# scHnRk_2.net
KiCad netlist of a schematic drawn in EAGLE
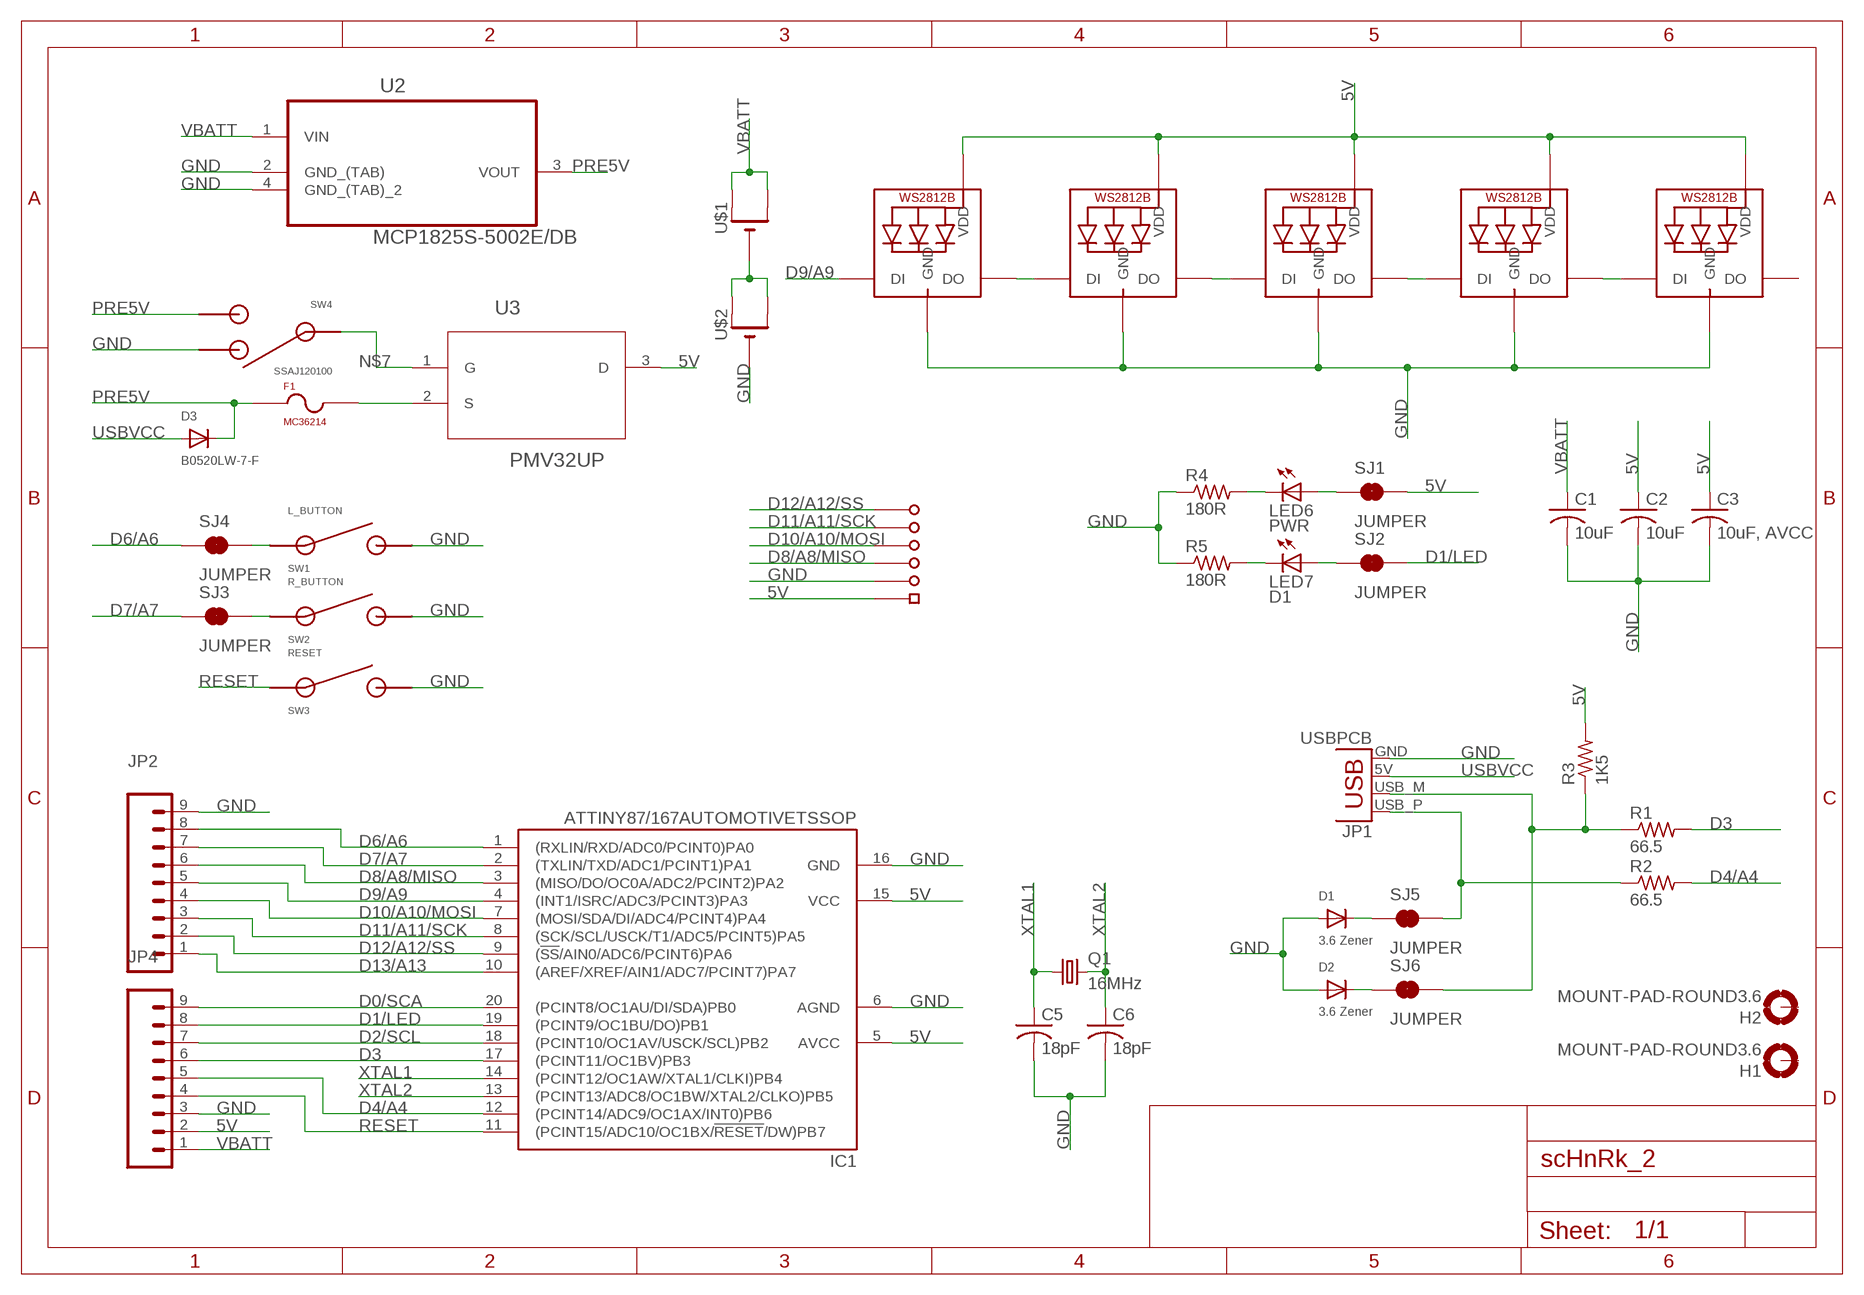
[diagram p0: schematic, sheet 1]

(export (version "E")
  (design (tool "Eeschema 10.0.6"))
  (components
    (comp (ref "C1")
      (value "10uF")
      (footprint "eagle-import:C1206K")
      (libsource (lib "eagle-import") (part "C-USC1206K"))
    )
    (comp (ref "C2")
      (value "10uF")
      (footprint "eagle-import:C1206K")
      (libsource (lib "eagle-import") (part "C-USC1206K"))
    )
    (comp (ref "C3")
      (value "10uF, AVCC")
      (footprint "eagle-import:C1206K")
      (libsource (lib "eagle-import") (part "C-USC1206K"))
    )
    (comp (ref "C5")
      (value "18pF")
      (footprint "eagle-import:C0603K")
      (libsource (lib "eagle-import") (part "C-USC0603K"))
    )
    (comp (ref "C6")
      (value "18pF")
      (footprint "eagle-import:C0603K")
      (libsource (lib "eagle-import") (part "C-USC0603K"))
    )
    (comp (ref "D1")
      (value "3.6 Zener")
      (footprint "eagle-import:SOD-523")
      (libsource (lib "eagle-import") (part "DIODESOD-523"))
    )
    (comp (ref "D2")
      (value "3.6 Zener")
      (footprint "eagle-import:SOD-523")
      (libsource (lib "eagle-import") (part "DIODESOD-523"))
    )
    (comp (ref "D3")
      (value "B0520LW-7-F")
      (footprint "eagle-import:SOD-123")
      (libsource (lib "eagle-import") (part "DIODESOD-123"))
    )
    (comp (ref "F1")
      (value "MC36214")
      (footprint "eagle-import:MC36214")
      (libsource (lib "eagle-import") (part "MC36214"))
    )
    (comp (ref "H1")
      (value "MOUNT-PAD-ROUND3.6")
      (footprint "eagle-import:3,6-PAD")
      (libsource (lib "eagle-import") (part "MOUNT-PAD-ROUND3.6"))
    )
    (comp (ref "H2")
      (value "MOUNT-PAD-ROUND3.6")
      (footprint "eagle-import:3,6-PAD")
      (libsource (lib "eagle-import") (part "MOUNT-PAD-ROUND3.6"))
    )
    (comp (ref "IC1")
      (value "ATTINY87/167AUTOMOTIVETSSOP")
      (footprint "eagle-import:TSSOP20")
      (libsource (lib "eagle-import") (part "ATTINY87/167AUTOMOTIVETSSOP"))
    )
    (comp (ref "JP1")
      (value "USBPCB")
      (footprint "eagle-import:USB-A-PCB")
      (libsource (lib "eagle-import") (part "USBPCB"))
    )
    (comp (ref "JP2")
      (value "M09")
      (footprint "eagle-import:1X09")
      (libsource (lib "eagle-import") (part "M09"))
    )
    (comp (ref "JP4")
      (value "M09")
      (footprint "eagle-import:1X09")
      (libsource (lib "eagle-import") (part "M09"))
    )
    (comp (ref "LED1")
      (value "WS2812B5050")
      (footprint "eagle-import:WS2812B")
      (libsource (lib "eagle-import") (part "WS2812B5050"))
    )
    (comp (ref "LED2")
      (value "WS2812B5050")
      (footprint "eagle-import:WS2812B")
      (libsource (lib "eagle-import") (part "WS2812B5050"))
    )
    (comp (ref "LED3")
      (value "WS2812B5050")
      (footprint "eagle-import:WS2812B")
      (libsource (lib "eagle-import") (part "WS2812B5050"))
    )
    (comp (ref "LED4")
      (value "WS2812B5050")
      (footprint "eagle-import:WS2812B")
      (libsource (lib "eagle-import") (part "WS2812B5050"))
    )
    (comp (ref "LED5")
      (value "WS2812B5050")
      (footprint "eagle-import:WS2812B")
      (libsource (lib "eagle-import") (part "WS2812B5050"))
    )
    (comp (ref "LED6")
      (value "PWR")
      (footprint "eagle-import:CHIPLED_0603")
      (libsource (lib "eagle-import") (part "LEDCHIPLED_0603"))
    )
    (comp (ref "LED7")
      (value "D1")
      (footprint "eagle-import:CHIPLED_0603")
      (libsource (lib "eagle-import") (part "LEDCHIPLED_0603"))
    )
    (comp (ref "Q1")
      (value "16MHz")
      (footprint "eagle-import:HC49UP")
      (libsource (lib "eagle-import") (part "CRYSTALHC49UP"))
    )
    (comp (ref "R1")
      (value "66.5")
      (footprint "eagle-import:R0603")
      (libsource (lib "eagle-import") (part "R-US_R0603"))
    )
    (comp (ref "R2")
      (value "66.5")
      (footprint "eagle-import:R0603")
      (libsource (lib "eagle-import") (part "R-US_R0603"))
    )
    (comp (ref "R3")
      (value "1K5")
      (footprint "eagle-import:R0603")
      (libsource (lib "eagle-import") (part "R-US_R0603"))
    )
    (comp (ref "R4")
      (value "180R")
      (footprint "eagle-import:R0603")
      (libsource (lib "eagle-import") (part "R-US_R0603"))
    )
    (comp (ref "R5")
      (value "180R")
      (footprint "eagle-import:R0603")
      (libsource (lib "eagle-import") (part "R-US_R0603"))
    )
    (comp (ref "SJ1")
      (value "JUMPER")
      (footprint "eagle-import:PAD-JUMPER-2-NC_BY_TRACE_YES_SILK")
      (libsource (lib "eagle-import") (part "JUMPER-PAD-2-NC_BY_TRACE"))
    )
    (comp (ref "SJ2")
      (value "JUMPER")
      (footprint "eagle-import:PAD-JUMPER-2-NC_BY_TRACE_YES_SILK")
      (libsource (lib "eagle-import") (part "JUMPER-PAD-2-NC_BY_TRACE"))
    )
    (comp (ref "SJ3")
      (value "JUMPER")
      (footprint "eagle-import:PAD-JUMPER-2-NC_BY_TRACE_YES_SILK")
      (libsource (lib "eagle-import") (part "JUMPER-PAD-2-NC_BY_TRACE"))
    )
    (comp (ref "SJ4")
      (value "JUMPER")
      (footprint "eagle-import:PAD-JUMPER-2-NC_BY_TRACE_YES_SILK")
      (libsource (lib "eagle-import") (part "JUMPER-PAD-2-NC_BY_TRACE"))
    )
    (comp (ref "SJ5")
      (value "JUMPER")
      (footprint "eagle-import:PAD-JUMPER-2-NC_BY_TRACE_YES_SILK")
      (libsource (lib "eagle-import") (part "JUMPER-PAD-2-NC_BY_TRACE"))
    )
    (comp (ref "SJ6")
      (value "JUMPER")
      (footprint "eagle-import:PAD-JUMPER-2-NC_BY_TRACE_YES_SILK")
      (libsource (lib "eagle-import") (part "JUMPER-PAD-2-NC_BY_TRACE"))
    )
    (comp (ref "SW1")
      (value "L_BUTTON")
      (footprint "eagle-import:SKRBAGE010")
      (libsource (lib "eagle-import") (part "SKRBAGE010"))
    )
    (comp (ref "SW2")
      (value "R_BUTTON")
      (footprint "eagle-import:SKRBAGE010")
      (libsource (lib "eagle-import") (part "SKRBAGE010"))
    )
    (comp (ref "SW3")
      (value "RESET")
      (footprint "eagle-import:SKRBAGE010")
      (libsource (lib "eagle-import") (part "SKRBAGE010"))
    )
    (comp (ref "SW4")
      (value "SSAJ120100")
      (footprint "eagle-import:SSAJ120100")
      (libsource (lib "eagle-import") (part "SSAJ120100"))
    )
    (comp (ref "TP1")
      (value "TP-R")
      (footprint "eagle-import:TP-R")
      (libsource (lib "eagle-import") (part "TP-R"))
    )
    (comp (ref "TP2")
      (value "TP-S")
      (footprint "eagle-import:TP_S")
      (libsource (lib "eagle-import") (part "TP-S"))
    )
    (comp (ref "TP3")
      (value "TP-R")
      (footprint "eagle-import:TP-R")
      (libsource (lib "eagle-import") (part "TP-R"))
    )
    (comp (ref "TP4")
      (value "TP-R")
      (footprint "eagle-import:TP-R")
      (libsource (lib "eagle-import") (part "TP-R"))
    )
    (comp (ref "TP5")
      (value "TP-R")
      (footprint "eagle-import:TP-R")
      (libsource (lib "eagle-import") (part "TP-R"))
    )
    (comp (ref "TP6")
      (value "TP-R")
      (footprint "eagle-import:TP-R")
      (libsource (lib "eagle-import") (part "TP-R"))
    )
    (comp (ref "U$1")
      (value "CR2032SMT")
      (footprint "eagle-import:CR2032-SMD")
      (libsource (lib "eagle-import") (part "CR2032SMT"))
    )
    (comp (ref "U$2")
      (value "CR2032SMT")
      (footprint "eagle-import:CR2032-SMD")
      (libsource (lib "eagle-import") (part "CR2032SMT"))
    )
    (comp (ref "U2")
      (value "MCP1825S-5002E/DB")
      (footprint "eagle-import:SOT230P700X180-4N")
      (libsource (lib "eagle-import") (part "MCP1825S-5002E/DB"))
    )
    (comp (ref "U3")
      (value "PMV32UP")
      (footprint "eagle-import:SOT95P230X110-3N")
      (libsource (lib "eagle-import") (part "PMV32UP"))
    )
  )
  (nets
    (net (code "1") (name "/5V") (class "Default")
      (node (ref "C2") (pin "1") (pinfunction "1_1") (pintype "passive"))
      (node (ref "C3") (pin "1") (pinfunction "1_1") (pintype "passive"))
      (node (ref "IC1") (pin "15") (pinfunction "VCC_15") (pintype "power_in"))
      (node (ref "IC1") (pin "5") (pinfunction "AVCC_5") (pintype "bidirectional"))
      (node (ref "JP4") (pin "2") (pinfunction "2_2") (pintype "passive"))
      (node (ref "LED1") (pin "1-VDD") (pinfunction "VDD_1-VDD") (pintype "power_in"))
      (node (ref "LED2") (pin "1-VDD") (pinfunction "VDD_1-VDD") (pintype "power_in"))
      (node (ref "LED3") (pin "1-VDD") (pinfunction "VDD_1-VDD") (pintype "power_in"))
      (node (ref "LED4") (pin "1-VDD") (pinfunction "VDD_1-VDD") (pintype "power_in"))
      (node (ref "LED5") (pin "1-VDD") (pinfunction "VDD_1-VDD") (pintype "power_in"))
      (node (ref "R3") (pin "2") (pinfunction "2_2") (pintype "passive"))
      (node (ref "SJ1") (pin "2") (pinfunction "2_2") (pintype "passive"))
      (node (ref "TP2") (pin "P$1") (pinfunction "P$1_P$1") (pintype "bidirectional"))
      (node (ref "U3") (pin "3") (pinfunction "D_3") (pintype "passive"))
    )
    (net (code "2") (name "/D0{slash}SCA") (class "Default")
      (node (ref "IC1") (pin "20") (pinfunction "(PCINT8/OC1AU/DI/SDA)PB0_20") (pintype "bidirectional"))
      (node (ref "JP4") (pin "9") (pinfunction "9_9") (pintype "passive"))
    )
    (net (code "3") (name "/D1{slash}LED") (class "Default")
      (node (ref "IC1") (pin "19") (pinfunction "(PCINT9/OC1BU/DO)PB1_19") (pintype "bidirectional"))
      (node (ref "JP4") (pin "8") (pinfunction "8_8") (pintype "passive"))
      (node (ref "SJ2") (pin "2") (pinfunction "2_2") (pintype "passive"))
    )
    (net (code "4") (name "/D2{slash}SCL") (class "Default")
      (node (ref "IC1") (pin "18") (pinfunction "(PCINT10/OC1AV/USCK/SCL)PB2_18") (pintype "bidirectional"))
      (node (ref "JP4") (pin "7") (pinfunction "7_7") (pintype "passive"))
    )
    (net (code "5") (name "/D3") (class "Default")
      (node (ref "IC1") (pin "17") (pinfunction "(PCINT11/OC1BV)PB3_17") (pintype "bidirectional"))
      (node (ref "JP4") (pin "6") (pinfunction "6_6") (pintype "passive"))
      (node (ref "R1") (pin "2") (pinfunction "2_2") (pintype "passive"))
    )
    (net (code "6") (name "/D4{slash}A4") (class "Default")
      (node (ref "IC1") (pin "12") (pinfunction "(PCINT14/ADC9/OC1AX/INT0)PB6_12") (pintype "bidirectional"))
      (node (ref "JP4") (pin "5") (pinfunction "5_5") (pintype "passive"))
      (node (ref "R2") (pin "2") (pinfunction "2_2") (pintype "passive"))
    )
    (net (code "7") (name "/D6{slash}A6") (class "Default")
      (node (ref "IC1") (pin "1") (pinfunction "(RXLIN/RXD/ADC0/PCINT0)PA0_1") (pintype "bidirectional"))
      (node (ref "JP2") (pin "8") (pinfunction "8_8") (pintype "passive"))
      (node (ref "SJ4") (pin "1") (pinfunction "1_1") (pintype "passive"))
    )
    (net (code "8") (name "/D7{slash}A7") (class "Default")
      (node (ref "IC1") (pin "2") (pinfunction "(TXLIN/TXD/ADC1/PCINT1)PA1_2") (pintype "bidirectional"))
      (node (ref "JP2") (pin "7") (pinfunction "7_7") (pintype "passive"))
      (node (ref "SJ3") (pin "1") (pinfunction "1_1") (pintype "passive"))
    )
    (net (code "9") (name "/D8{slash}A8{slash}MISO") (class "Default")
      (node (ref "IC1") (pin "3") (pinfunction "(MISO/DO/OC0A/ADC2/PCINT2)PA2_3") (pintype "bidirectional"))
      (node (ref "JP2") (pin "6") (pinfunction "6_6") (pintype "passive"))
      (node (ref "TP3") (pin "P$1") (pinfunction "P$1_P$1") (pintype "bidirectional"))
    )
    (net (code "10") (name "/D9{slash}A9") (class "Default")
      (node (ref "IC1") (pin "4") (pinfunction "(INT1/ISRC/ADC3/PCINT3)PA3_4") (pintype "bidirectional"))
      (node (ref "JP2") (pin "5") (pinfunction "5_5") (pintype "passive"))
      (node (ref "LED1") (pin "4-DIN") (pinfunction "DI_4-DIN") (pintype "input"))
    )
    (net (code "11") (name "/D10{slash}A10{slash}MOSI") (class "Default")
      (node (ref "IC1") (pin "7") (pinfunction "(MOSI/SDA/DI/ADC4/PCINT4)PA4_7") (pintype "bidirectional"))
      (node (ref "JP2") (pin "4") (pinfunction "4_4") (pintype "passive"))
      (node (ref "TP4") (pin "P$1") (pinfunction "P$1_P$1") (pintype "bidirectional"))
    )
    (net (code "12") (name "/D11{slash}A11{slash}SCK") (class "Default")
      (node (ref "IC1") (pin "8") (pinfunction "(SCK/SCL/USCK/T1/ADC5/PCINT5)PA5_8") (pintype "bidirectional"))
      (node (ref "JP2") (pin "3") (pinfunction "3_3") (pintype "passive"))
      (node (ref "TP5") (pin "P$1") (pinfunction "P$1_P$1") (pintype "bidirectional"))
    )
    (net (code "13") (name "/D12{slash}A12{slash}SS") (class "Default")
      (node (ref "IC1") (pin "9") (pinfunction "(~{SS}/AIN0/ADC6/PCINT6)PA6_9") (pintype "bidirectional"))
      (node (ref "JP2") (pin "2") (pinfunction "2_2") (pintype "passive"))
      (node (ref "TP6") (pin "P$1") (pinfunction "P$1_P$1") (pintype "bidirectional"))
    )
    (net (code "14") (name "/D13{slash}A13") (class "Default")
      (node (ref "IC1") (pin "10") (pinfunction "(AREF/XREF/AIN1/ADC7/PCINT7)PA7_10") (pintype "bidirectional"))
      (node (ref "JP2") (pin "1") (pinfunction "1_1") (pintype "passive"))
    )
    (net (code "15") (name "/GND") (class "Default")
      (node (ref "C1") (pin "2") (pinfunction "2_2") (pintype "passive"))
      (node (ref "C2") (pin "2") (pinfunction "2_2") (pintype "passive"))
      (node (ref "C3") (pin "2") (pinfunction "2_2") (pintype "passive"))
      (node (ref "C5") (pin "2") (pinfunction "2_2") (pintype "passive"))
      (node (ref "C6") (pin "2") (pinfunction "2_2") (pintype "passive"))
      (node (ref "D1") (pin "A") (pinfunction "A_A") (pintype "passive"))
      (node (ref "D2") (pin "A") (pinfunction "A_A") (pintype "passive"))
      (node (ref "IC1") (pin "16") (pinfunction "GND_16") (pintype "power_in"))
      (node (ref "IC1") (pin "6") (pinfunction "AGND_6") (pintype "bidirectional"))
      (node (ref "JP1") (pin "GND") (pinfunction "GND_GND") (pintype "bidirectional"))
      (node (ref "JP2") (pin "9") (pinfunction "9_9") (pintype "passive"))
      (node (ref "JP4") (pin "3") (pinfunction "3_3") (pintype "passive"))
      (node (ref "LED1") (pin "3-GND") (pinfunction "GND_3-GND") (pintype "power_in"))
      (node (ref "LED2") (pin "3-GND") (pinfunction "GND_3-GND") (pintype "power_in"))
      (node (ref "LED3") (pin "3-GND") (pinfunction "GND_3-GND") (pintype "power_in"))
      (node (ref "LED4") (pin "3-GND") (pinfunction "GND_3-GND") (pintype "power_in"))
      (node (ref "LED5") (pin "3-GND") (pinfunction "GND_3-GND") (pintype "power_in"))
      (node (ref "R4") (pin "1") (pinfunction "1_1") (pintype "passive"))
      (node (ref "R5") (pin "1") (pinfunction "1_1") (pintype "passive"))
      (node (ref "SW1") (pin "P$2") (pinfunction "P$2_P$2") (pintype "bidirectional"))
      (node (ref "SW1") (pin "P$4") (pinfunction "P$2_P$4") (pintype "bidirectional"))
      (node (ref "SW2") (pin "P$2") (pinfunction "P$2_P$2") (pintype "bidirectional"))
      (node (ref "SW2") (pin "P$4") (pinfunction "P$2_P$4") (pintype "bidirectional"))
      (node (ref "SW3") (pin "P$2") (pinfunction "P$2_P$2") (pintype "bidirectional"))
      (node (ref "SW3") (pin "P$4") (pinfunction "P$2_P$4") (pintype "bidirectional"))
      (node (ref "SW4") (pin "P$1") (pinfunction "P$1_P$1") (pintype "bidirectional"))
      (node (ref "TP1") (pin "P$1") (pinfunction "P$1_P$1") (pintype "bidirectional"))
      (node (ref "U$2") (pin "-") (pinfunction "-_-") (pintype "passive"))
      (node (ref "U2") (pin "2") (pinfunction "GND_(TAB)_2") (pintype "passive"))
      (node (ref "U2") (pin "4") (pinfunction "GND_(TAB)_2_4") (pintype "passive"))
    )
    (net (code "16") (name "/N$7") (class "Default")
      (node (ref "SW4") (pin "P$C") (pinfunction "P$C_P$C") (pintype "bidirectional"))
      (node (ref "U3") (pin "1") (pinfunction "G_1") (pintype "passive"))
    )
    (net (code "17") (name "/PRE5V") (class "Default")
      (node (ref "D3") (pin "C") (pinfunction "C_C") (pintype "passive"))
      (node (ref "F1") (pin "P$1") (pinfunction "P$1_P$1") (pintype "bidirectional"))
      (node (ref "SW4") (pin "P$2") (pinfunction "P$2_P$2") (pintype "bidirectional"))
      (node (ref "U2") (pin "3") (pinfunction "VOUT_3") (pintype "output"))
    )
    (net (code "18") (name "/RESET") (class "Default")
      (node (ref "IC1") (pin "11") (pinfunction "(PCINT15/ADC10/OC1BX/~{RESET}/DW)PB7_11") (pintype "bidirectional"))
      (node (ref "JP4") (pin "4") (pinfunction "4_4") (pintype "passive"))
      (node (ref "SW3") (pin "P$1") (pinfunction "P$1_P$1") (pintype "bidirectional"))
      (node (ref "SW3") (pin "P$3") (pinfunction "P$1_P$3") (pintype "bidirectional"))
    )
    (net (code "19") (name "/USBVCC") (class "Default")
      (node (ref "D3") (pin "A") (pinfunction "A_A") (pintype "passive"))
      (node (ref "JP1") (pin "5V") (pinfunction "VBUS_5V") (pintype "bidirectional"))
    )
    (net (code "20") (name "/VBATT") (class "Default")
      (node (ref "C1") (pin "1") (pinfunction "1_1") (pintype "passive"))
      (node (ref "JP4") (pin "1") (pinfunction "1_1") (pintype "passive"))
      (node (ref "U$1") (pin "+$1") (pinfunction "+_+$1") (pintype "passive"))
      (node (ref "U$1") (pin "+$2") (pinfunction "+1_+$2") (pintype "passive"))
      (node (ref "U2") (pin "1") (pinfunction "VIN_1") (pintype "input"))
    )
    (net (code "21") (name "/XTAL1") (class "Default")
      (node (ref "C5") (pin "1") (pinfunction "1_1") (pintype "passive"))
      (node (ref "IC1") (pin "14") (pinfunction "(PCINT12/OC1AW/XTAL1/CLKI)PB4_14") (pintype "bidirectional"))
      (node (ref "Q1") (pin "1") (pinfunction "1_1") (pintype "passive"))
    )
    (net (code "22") (name "/XTAL2") (class "Default")
      (node (ref "C6") (pin "1") (pinfunction "1_1") (pintype "passive"))
      (node (ref "IC1") (pin "13") (pinfunction "(PCINT13/ADC8/OC1BW/XTAL2/CLKO)PB5_13") (pintype "bidirectional"))
      (node (ref "Q1") (pin "2") (pinfunction "2_2") (pintype "passive"))
    )
    (net (code "23") (name "Net-(D1-C)") (class "Default")
      (node (ref "D1") (pin "K") (pinfunction "C_K") (pintype "passive"))
      (node (ref "SJ5") (pin "1") (pinfunction "1_1") (pintype "passive"))
    )
    (net (code "24") (name "Net-(D2-C)") (class "Default")
      (node (ref "D2") (pin "K") (pinfunction "C_K") (pintype "passive"))
      (node (ref "SJ6") (pin "1") (pinfunction "1_1") (pintype "passive"))
    )
    (net (code "25") (name "Net-(JP1-D+)") (class "Default")
      (node (ref "JP1") (pin "USB_P") (pinfunction "D+_USB_P") (pintype "bidirectional"))
      (node (ref "R2") (pin "1") (pinfunction "1_1") (pintype "passive"))
      (node (ref "SJ5") (pin "2") (pinfunction "2_2") (pintype "passive"))
    )
    (net (code "26") (name "Net-(JP1-D-)") (class "Default")
      (node (ref "JP1") (pin "USB_M") (pinfunction "D-_USB_M") (pintype "bidirectional"))
      (node (ref "R1") (pin "1") (pinfunction "1_1") (pintype "passive"))
      (node (ref "R3") (pin "1") (pinfunction "1_1") (pintype "passive"))
      (node (ref "SJ6") (pin "2") (pinfunction "2_2") (pintype "passive"))
    )
    (net (code "27") (name "Net-(LED1-DO)") (class "Default")
      (node (ref "LED1") (pin "2-DOUT") (pinfunction "DO_2-DOUT") (pintype "output"))
      (node (ref "LED2") (pin "4-DIN") (pinfunction "DI_4-DIN") (pintype "input"))
    )
    (net (code "28") (name "Net-(LED2-DO)") (class "Default")
      (node (ref "LED2") (pin "2-DOUT") (pinfunction "DO_2-DOUT") (pintype "output"))
      (node (ref "LED3") (pin "4-DIN") (pinfunction "DI_4-DIN") (pintype "input"))
    )
    (net (code "29") (name "Net-(LED3-DO)") (class "Default")
      (node (ref "LED3") (pin "2-DOUT") (pinfunction "DO_2-DOUT") (pintype "output"))
      (node (ref "LED4") (pin "4-DIN") (pinfunction "DI_4-DIN") (pintype "input"))
    )
    (net (code "30") (name "Net-(LED4-DO)") (class "Default")
      (node (ref "LED4") (pin "2-DOUT") (pinfunction "DO_2-DOUT") (pintype "output"))
      (node (ref "LED5") (pin "4-DIN") (pinfunction "DI_4-DIN") (pintype "input"))
    )
    (net (code "31") (name "Net-(LED6-PadA)") (class "Default")
      (node (ref "LED6") (pin "A") (pinfunction "A_A") (pintype "passive"))
      (node (ref "SJ1") (pin "1") (pinfunction "1_1") (pintype "passive"))
    )
    (net (code "32") (name "Net-(LED6-PadC)") (class "Default")
      (node (ref "LED6") (pin "C") (pinfunction "C_C") (pintype "passive"))
      (node (ref "R4") (pin "2") (pinfunction "2_2") (pintype "passive"))
    )
    (net (code "33") (name "Net-(LED7-PadA)") (class "Default")
      (node (ref "LED7") (pin "A") (pinfunction "A_A") (pintype "passive"))
      (node (ref "SJ2") (pin "1") (pinfunction "1_1") (pintype "passive"))
    )
    (net (code "34") (name "Net-(LED7-PadC)") (class "Default")
      (node (ref "LED7") (pin "C") (pinfunction "C_C") (pintype "passive"))
      (node (ref "R5") (pin "2") (pinfunction "2_2") (pintype "passive"))
    )
    (net (code "35") (name "Net-(SJ3-Pad2)") (class "Default")
      (node (ref "SJ3") (pin "2") (pinfunction "2_2") (pintype "passive"))
      (node (ref "SW2") (pin "P$1") (pinfunction "P$1_P$1") (pintype "bidirectional"))
      (node (ref "SW2") (pin "P$3") (pinfunction "P$1_P$3") (pintype "bidirectional"))
    )
    (net (code "36") (name "Net-(SJ4-Pad2)") (class "Default")
      (node (ref "SJ4") (pin "2") (pinfunction "2_2") (pintype "passive"))
      (node (ref "SW1") (pin "P$1") (pinfunction "P$1_P$1") (pintype "bidirectional"))
      (node (ref "SW1") (pin "P$3") (pinfunction "P$1_P$3") (pintype "bidirectional"))
    )
    (net (code "37") (name "Net-(U$2-+)") (class "Default")
      (node (ref "U$1") (pin "-") (pinfunction "-_-") (pintype "passive"))
      (node (ref "U$2") (pin "+$1") (pinfunction "+_+$1") (pintype "passive"))
      (node (ref "U$2") (pin "+$2") (pinfunction "+1_+$2") (pintype "passive"))
    )
    (net (code "38") (name "Net-(U3-S)") (class "Default")
      (node (ref "F1") (pin "P$2") (pinfunction "P$2_P$2") (pintype "bidirectional"))
      (node (ref "U3") (pin "2") (pinfunction "S_2") (pintype "passive"))
    )
    (net (code "39") (name "unconnected-(H1-MOUNT-PadB3,6)") (class "Default")
      (node (ref "H1") (pin "B3,6") (pinfunction "MOUNT_B3,6") (pintype "passive"))
    )
    (net (code "40") (name "unconnected-(H2-MOUNT-PadB3,6)") (class "Default")
      (node (ref "H2") (pin "B3,6") (pinfunction "MOUNT_B3,6") (pintype "passive"))
    )
    (net (code "41") (name "unconnected-(LED5-DO-Pad2-DOUT)") (class "Default")
      (node (ref "LED5") (pin "2-DOUT") (pinfunction "DO_2-DOUT") (pintype "output"))
    )
  )
)
